# light_emitter.net
KiCad netlist of a schematic drawn in EAGLE
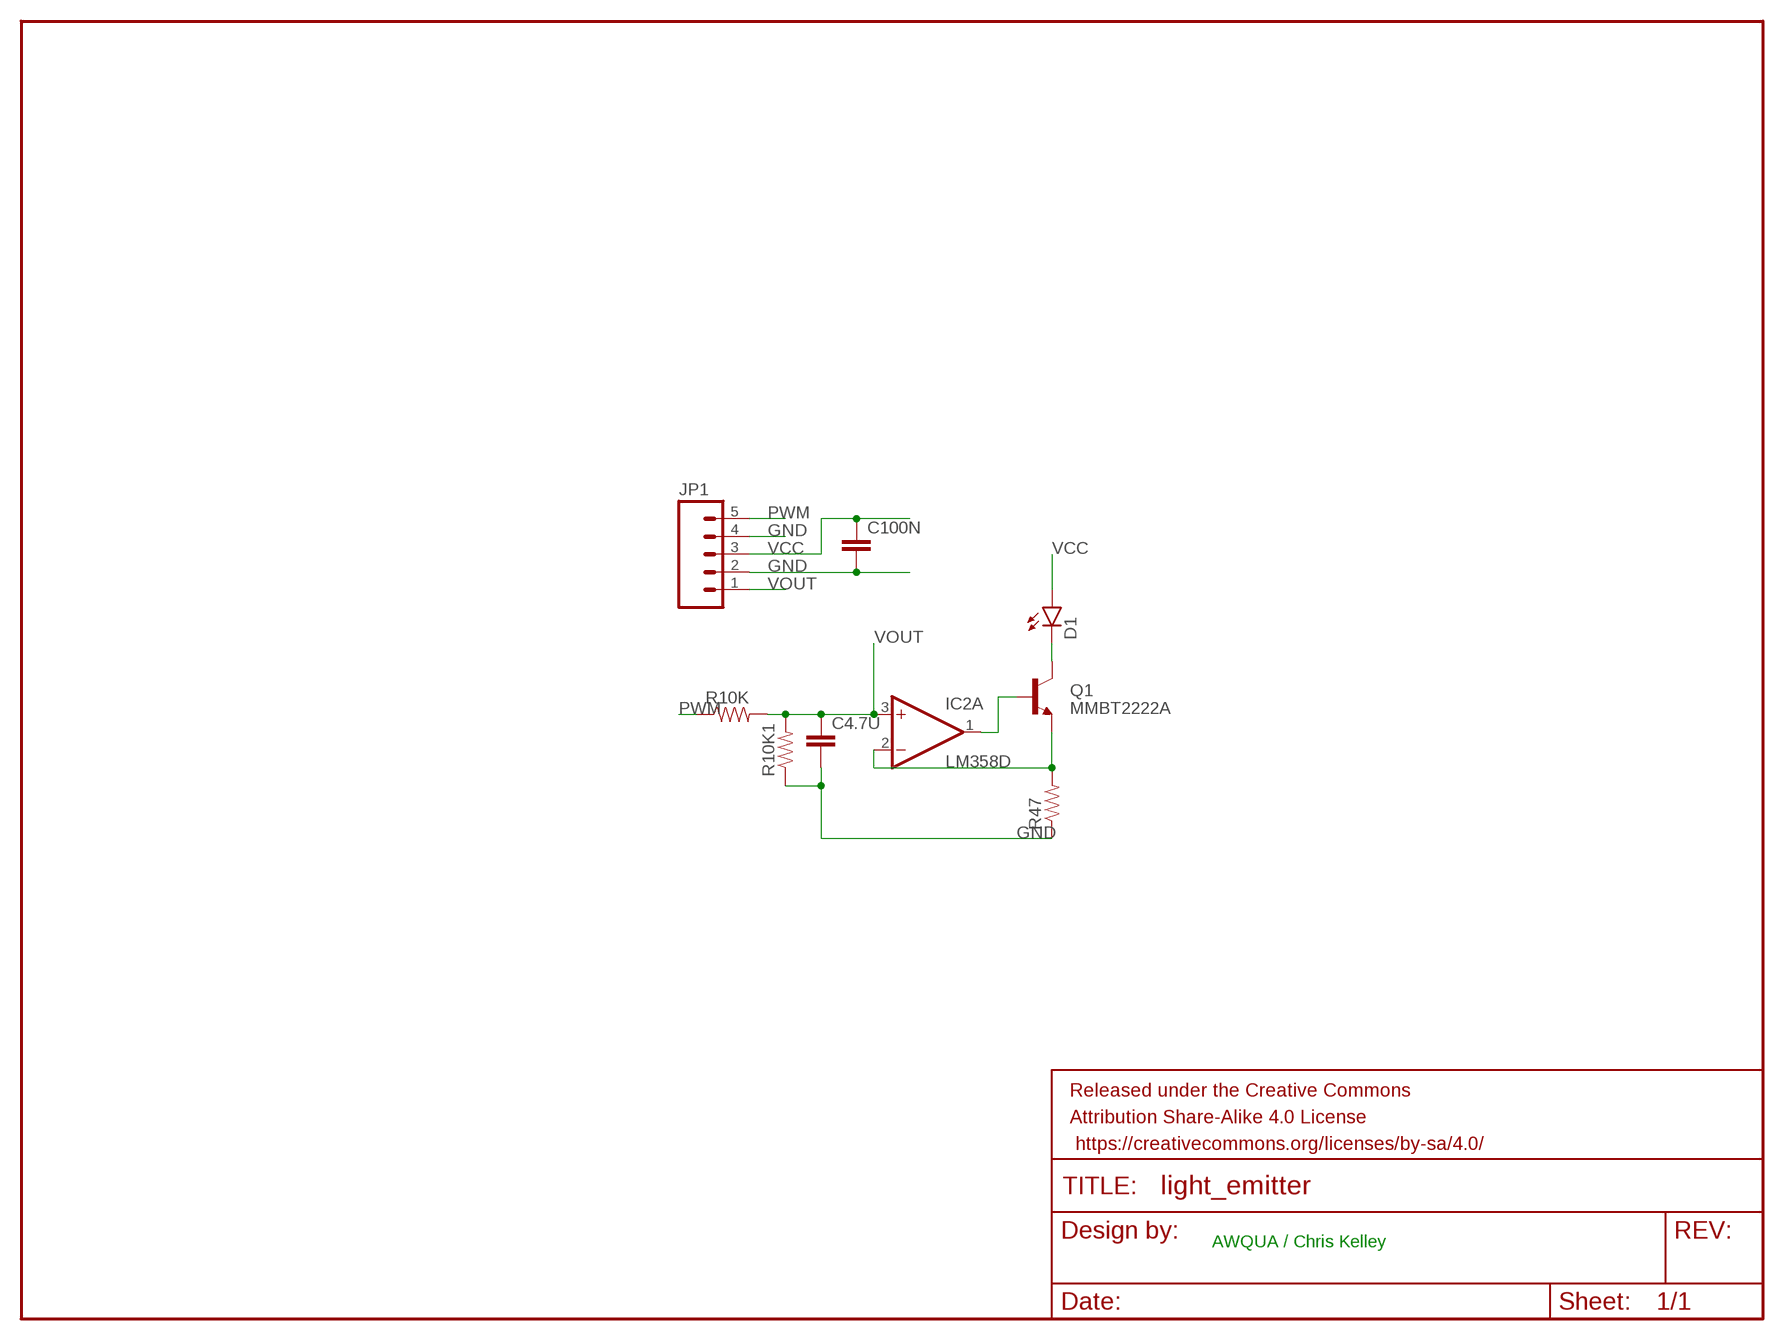
[diagram p0: schematic, sheet 1]

(export (version "E")
  (design (tool "Eeschema 10.0.6"))
  (components
    (comp (ref "C4.7U")
      (value "CAP0603-CAP")
      (footprint "eagle-import:0603-CAP")
      (libsource (lib "eagle-import") (part "CAP0603-CAP"))
    )
    (comp (ref "C100N")
      (value "CAP0603-CAP")
      (footprint "eagle-import:0603-CAP")
      (libsource (lib "eagle-import") (part "CAP0603-CAP"))
    )
    (comp (ref "D1")
      (value "LED5MM")
      (footprint "eagle-import:LED5MM")
      (libsource (lib "eagle-import") (part "LED5MM"))
    )
    (comp (ref "FRAME1")
      (value "FRAME-LETTER")
      (footprint "eagle-import:CREATIVE_COMMONS")
      (libsource (lib "eagle-import") (part "FRAME-LETTER"))
    )
    (comp (ref "IC2")
      (value "LM358D")
      (footprint "eagle-import:SO08")
      (libsource (lib "eagle-import") (part "LM358D"))
    )
    (comp (ref "JP1")
      (value "M05PTH")
      (footprint "eagle-import:1X05")
      (libsource (lib "eagle-import") (part "M05PTH"))
    )
    (comp (ref "Q1")
      (value "MMBT2222A")
      (footprint "eagle-import:SOT23-3")
      (libsource (lib "eagle-import") (part "TRANSISTOR_NPNMMBT2222A"))
    )
    (comp (ref "R10K")
      (value "RESISTOR0603-RES")
      (footprint "eagle-import:0603-RES")
      (libsource (lib "eagle-import") (part "RESISTOR0603-RES"))
    )
    (comp (ref "R10K1")
      (value "RESISTOR0603-RES")
      (footprint "eagle-import:0603-RES")
      (libsource (lib "eagle-import") (part "RESISTOR0603-RES"))
    )
    (comp (ref "R47")
      (value "RESISTOR0603-RES")
      (footprint "eagle-import:0603-RES")
      (libsource (lib "eagle-import") (part "RESISTOR0603-RES"))
    )
  )
  (nets
    (net (code "1") (name "/GND") (class "Default")
      (node (ref "C100N") (pin "2") (pinfunction "2_2") (pintype "passive"))
      (node (ref "C4.7U") (pin "2") (pinfunction "2_2") (pintype "passive"))
      (node (ref "JP1") (pin "2") (pinfunction "2_2") (pintype "passive"))
      (node (ref "JP1") (pin "4") (pinfunction "4_4") (pintype "passive"))
      (node (ref "R10K1") (pin "1") (pinfunction "1_1") (pintype "passive"))
      (node (ref "R47") (pin "1") (pinfunction "1_1") (pintype "passive"))
    )
    (net (code "2") (name "/PWM") (class "Default")
      (node (ref "JP1") (pin "5") (pinfunction "5_5") (pintype "passive"))
      (node (ref "R10K") (pin "1") (pinfunction "1_1") (pintype "passive"))
    )
    (net (code "3") (name "/VCC") (class "Default")
      (node (ref "C100N") (pin "1") (pinfunction "1_1") (pintype "passive"))
      (node (ref "D1") (pin "A") (pinfunction "A_A") (pintype "passive"))
      (node (ref "JP1") (pin "3") (pinfunction "3_3") (pintype "passive"))
    )
    (net (code "4") (name "/VOUT") (class "Default")
      (node (ref "C4.7U") (pin "1") (pinfunction "1_1") (pintype "passive"))
      (node (ref "IC2") (pin "3") (pinfunction "+IN_3") (pintype "input"))
      (node (ref "JP1") (pin "1") (pinfunction "1_1") (pintype "passive"))
      (node (ref "R10K") (pin "2") (pinfunction "2_2") (pintype "passive"))
      (node (ref "R10K1") (pin "2") (pinfunction "2_2") (pintype "passive"))
    )
    (net (code "5") (name "Net-(D1-C)") (class "Default")
      (node (ref "D1") (pin "K") (pinfunction "C_K") (pintype "passive"))
      (node (ref "Q1") (pin "3") (pinfunction "C_3") (pintype "passive"))
    )
    (net (code "6") (name "Net-(IC2A--IN)") (class "Default")
      (node (ref "IC2") (pin "2") (pinfunction "-IN_2") (pintype "input"))
      (node (ref "Q1") (pin "2") (pinfunction "E_2") (pintype "passive"))
      (node (ref "R47") (pin "2") (pinfunction "2_2") (pintype "passive"))
    )
    (net (code "7") (name "Net-(IC2A-OUT)") (class "Default")
      (node (ref "IC2") (pin "1") (pinfunction "OUT_1") (pintype "output"))
      (node (ref "Q1") (pin "1") (pinfunction "B_1") (pintype "passive"))
    )
  )
)
